# RS485.net
KiCad netlist of a schematic drawn in Altium Designer
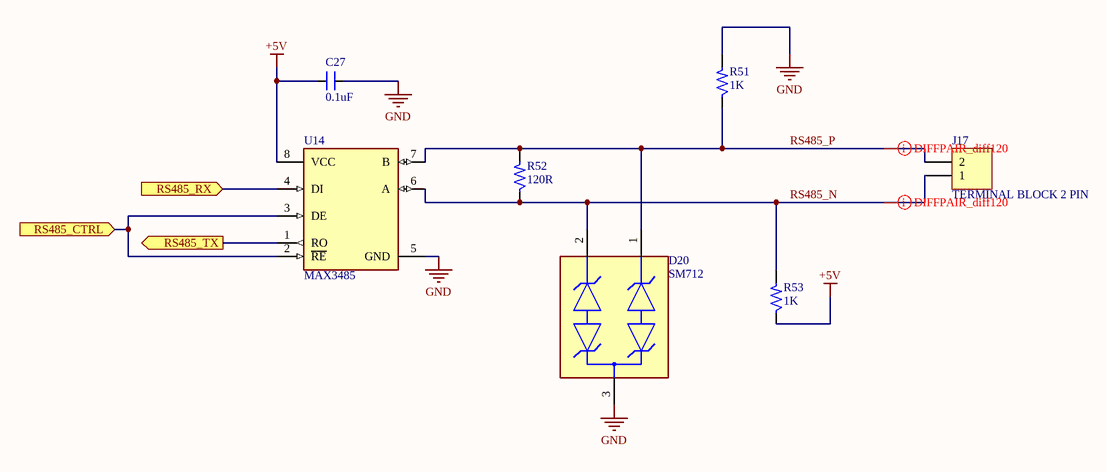
[diagram p0: RS485.SchDoc]

(export (version "E")
  (design (tool "Eeschema 10.0.6"))
  (components
    (comp (ref "C27")
      (value "0.1uF")
      (footprint "CAP_0805")
      (description "0.1µF ±5% 50V Ceramic Capacitor X7R 0805 (2012 Metric)")
      (fields
        (field (name "MANUFACTURER") "AVX Corporation")
        (field (name "MANUFACTURER PART NUMBER") "08055C104JAT4A")
      )
      (libsource (lib "ESTEEMPCBLIB") (part "CAP_0.1uF-50V-5%-0805"))
    )
    (comp (ref "D20")
      (value "SM712")
      (footprint "FP-SM712-MFG")
      (description "TVS DIODE 12V 31V SOT23-3")
      (libsource (lib "TAREKPCBLIB") (part "SM712-02HTG"))
    )
    (comp (ref "J17")
      (value "TERMINAL BLOCK 2 PIN")
      (footprint "CON2_P196_1729128_TH_ST")
      (description "2 Pins, 1 Row 5mm Pitch, straight Connector, male")
      (fields
        (field (name "MANUFACTURER") "Phoenix Contact")
        (field (name "MANUFACTURER PART NUMBER") "MKDSN1,5/2")
      )
      (libsource (lib "ESTEEMPCBLIB") (part "CON-TB_2X1-196-ST-TH"))
    )
    (comp (ref "R51")
      (value "1K")
      (footprint "RES_0805")
      (description "1 kOhms ±1% 0.125W, 1/8W Chip Resistor 0805 (2012 Metric) Moisture Resistant Thick Film")
      (fields (field (name "MANUFACTURER") "Walsin") (field (name "MANUFACTURER PART NUMBER") "WR08X1001FTL"))
      (libsource (lib "ESTEEMPCBLIB") (part "RES_1K-0.125W-1%-0805"))
    )
    (comp (ref "R52")
      (value "120R")
      (footprint "RES_0805")
      (fields
        (field (name "MANUFACTURER") "Stackpole Electronics")
        (field (name "MANUFACTURER PART NUMBER") "CRGCQ0805F120R")
      )
      (libsource (lib "ESTEEMPCBLIB") (part "RES_120R-0.125W-1%-0805"))
    )
    (comp (ref "R53")
      (value "1K")
      (footprint "RES_0805")
      (description "1 kOhms ±1% 0.125W, 1/8W Chip Resistor 0805 (2012 Metric) Moisture Resistant Thick Film")
      (fields (field (name "MANUFACTURER") "Walsin") (field (name "MANUFACTURER PART NUMBER") "WR08X1001FTL"))
      (libsource (lib "ESTEEMPCBLIB") (part "RES_1K-0.125W-1%-0805"))
    )
    (comp (ref "U14")
      (value "MAX3485")
      (footprint "FP-S8-5-IPC_C")
      (description "IC TXRX RS485/422 10MBPS 8SOIC")
      (fields
        (field (name "OCTOPART") "https://octopart.com/max3485esa%2B-maxim+integrated-39731860")
        (field (name "MANUFACTURER") "Maxim Integrated")
      )
      (libsource (lib "TAREKPCBLIB") (part "MAX3485ESA+"))
    )
  )
  (nets
    (net (code "1") (name "+5V") (class "Default")
      (node (ref "C27") (pin "2") (pinfunction "2_2") (pintype "passive"))
      (node (ref "R53") (pin "1") (pinfunction "1_1") (pintype "passive"))
      (node (ref "U14") (pin "8") (pinfunction "VCC_8") (pintype "power_in"))
    )
    (net (code "2") (name "/RS485_CTRL") (class "Default")
      (node (ref "U14") (pin "2") (pinfunction "~{RE}_2") (pintype "input"))
      (node (ref "U14") (pin "3") (pinfunction "DE_3") (pintype "input"))
    )
    (net (code "3") (name "/RS485_N") (class "Default")
      (node (ref "D20") (pin "2") (pinfunction "2_2") (pintype "passive"))
      (node (ref "J17") (pin "1") (pinfunction "1_1") (pintype "passive"))
      (node (ref "R52") (pin "1") (pinfunction "1_1") (pintype "passive"))
      (node (ref "R53") (pin "2") (pinfunction "2_2") (pintype "passive"))
      (node (ref "U14") (pin "6") (pinfunction "A_6") (pintype "bidirectional"))
    )
    (net (code "4") (name "/RS485_P") (class "Default")
      (node (ref "D20") (pin "1") (pinfunction "1_1") (pintype "passive"))
      (node (ref "J17") (pin "2") (pinfunction "2_2") (pintype "passive"))
      (node (ref "R51") (pin "1") (pinfunction "1_1") (pintype "passive"))
      (node (ref "R52") (pin "2") (pinfunction "2_2") (pintype "passive"))
      (node (ref "U14") (pin "7") (pinfunction "B_7") (pintype "bidirectional"))
    )
    (net (code "5") (name "/RS485_RX") (class "Default")
      (node (ref "U14") (pin "4") (pinfunction "DI_4") (pintype "input"))
    )
    (net (code "6") (name "/RS485_TX") (class "Default")
      (node (ref "U14") (pin "1") (pinfunction "RO_1") (pintype "output"))
    )
    (net (code "7") (name "GND") (class "Default")
      (node (ref "C27") (pin "1") (pinfunction "1_1") (pintype "passive"))
      (node (ref "D20") (pin "3") (pinfunction "3_3") (pintype "passive"))
      (node (ref "R51") (pin "2") (pinfunction "2_2") (pintype "passive"))
      (node (ref "U14") (pin "5") (pinfunction "GND_5") (pintype "power_in"))
    )
  )
)
